# nm_temp_sens.net
KiCad netlist of a schematic drawn in Altium Designer
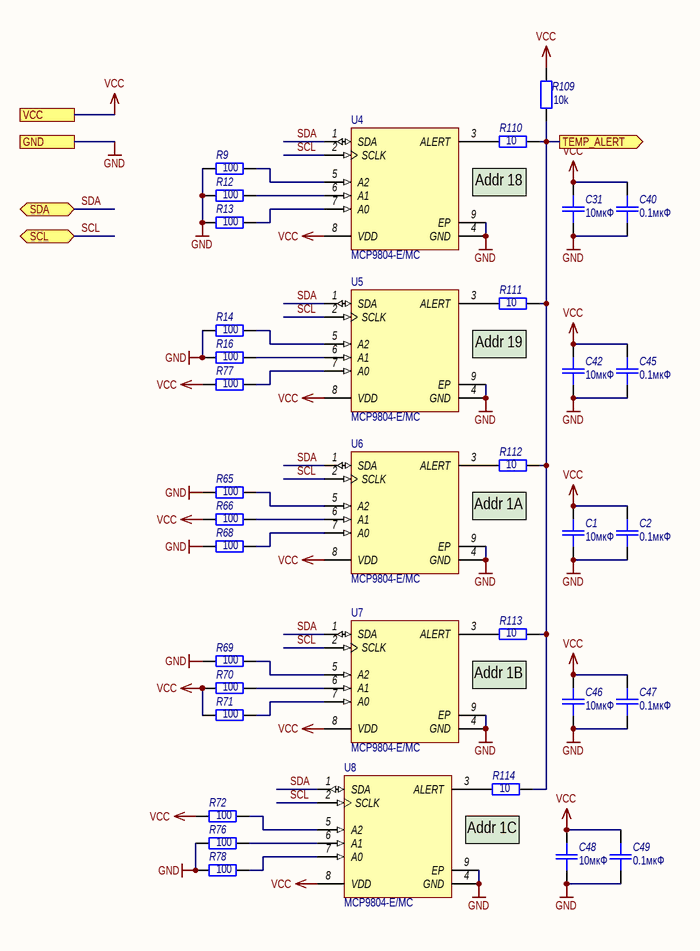
[diagram p0: nm_temp_sens.SchDoc]

(export (version "E")
  (design (tool "Eeschema 10.0.6"))
  (components
    (comp (ref "C1")
      (value "10мкФ")
      (footprint "SMD_C0603")
      (description "Capacitor")
      (libsource (lib "Passive") (part "Capacitor"))
    )
    (comp (ref "C2")
      (value "0.1мкФ")
      (footprint "SMD_C0603")
      (description "Capacitor")
      (libsource (lib "Passive") (part "Capacitor"))
    )
    (comp (ref "C31")
      (value "10мкФ")
      (footprint "SMD_C0603")
      (description "Capacitor")
      (libsource (lib "Passive") (part "Capacitor"))
    )
    (comp (ref "C40")
      (value "0.1мкФ")
      (footprint "SMD_C0603")
      (description "Capacitor")
      (libsource (lib "Passive") (part "Capacitor"))
    )
    (comp (ref "C42")
      (value "10мкФ")
      (footprint "SMD_C0603")
      (description "Capacitor")
      (libsource (lib "Passive") (part "Capacitor"))
    )
    (comp (ref "C45")
      (value "0.1мкФ")
      (footprint "SMD_C0603")
      (description "Capacitor")
      (libsource (lib "Passive") (part "Capacitor"))
    )
    (comp (ref "C46")
      (value "10мкФ")
      (footprint "SMD_C0603")
      (description "Capacitor")
      (libsource (lib "Passive") (part "Capacitor"))
    )
    (comp (ref "C47")
      (value "0.1мкФ")
      (footprint "SMD_C0603")
      (description "Capacitor")
      (libsource (lib "Passive") (part "Capacitor"))
    )
    (comp (ref "C48")
      (value "10мкФ")
      (footprint "SMD_C0603")
      (description "Capacitor")
      (libsource (lib "Passive") (part "Capacitor"))
    )
    (comp (ref "C49")
      (value "0.1мкФ")
      (footprint "SMD_C0603")
      (description "Capacitor")
      (libsource (lib "Passive") (part "Capacitor"))
    )
    (comp (ref "R9")
      (value "100")
      (footprint "SMD_0603")
      (description "Resistor")
      (libsource (lib "Passive") (part "Resistor"))
    )
    (comp (ref "R12")
      (value "100")
      (footprint "SMD_0603")
      (description "Resistor")
      (libsource (lib "Passive") (part "Resistor"))
    )
    (comp (ref "R13")
      (value "100")
      (footprint "SMD_0603")
      (description "Resistor")
      (libsource (lib "Passive") (part "Resistor"))
    )
    (comp (ref "R14")
      (value "100")
      (footprint "SMD_0603")
      (description "Resistor")
      (libsource (lib "Passive") (part "Resistor"))
    )
    (comp (ref "R16")
      (value "100")
      (footprint "SMD_0603")
      (description "Resistor")
      (libsource (lib "Passive") (part "Resistor"))
    )
    (comp (ref "R65")
      (value "100")
      (footprint "SMD_0603")
      (description "Resistor")
      (libsource (lib "Passive") (part "Resistor"))
    )
    (comp (ref "R66")
      (value "100")
      (footprint "SMD_0603")
      (description "Resistor")
      (libsource (lib "Passive") (part "Resistor"))
    )
    (comp (ref "R68")
      (value "100")
      (footprint "SMD_0603")
      (description "Resistor")
      (libsource (lib "Passive") (part "Resistor"))
    )
    (comp (ref "R69")
      (value "100")
      (footprint "SMD_0603")
      (description "Resistor")
      (libsource (lib "Passive") (part "Resistor"))
    )
    (comp (ref "R70")
      (value "100")
      (footprint "SMD_0603")
      (description "Resistor")
      (libsource (lib "Passive") (part "Resistor"))
    )
    (comp (ref "R71")
      (value "100")
      (footprint "SMD_0603")
      (description "Resistor")
      (libsource (lib "Passive") (part "Resistor"))
    )
    (comp (ref "R72")
      (value "100")
      (footprint "SMD_0603")
      (description "Resistor")
      (libsource (lib "Passive") (part "Resistor"))
    )
    (comp (ref "R76")
      (value "100")
      (footprint "SMD_0603")
      (description "Resistor")
      (libsource (lib "Passive") (part "Resistor"))
    )
    (comp (ref "R77")
      (value "100")
      (footprint "SMD_0603")
      (description "Resistor")
      (libsource (lib "Passive") (part "Resistor"))
    )
    (comp (ref "R78")
      (value "100")
      (footprint "SMD_0603")
      (description "Resistor")
      (libsource (lib "Passive") (part "Resistor"))
    )
    (comp (ref "R109")
      (value "10k")
      (footprint "SMD_0603")
      (description "Resistor")
      (libsource (lib "") (part "Resistor_1"))
    )
    (comp (ref "R110")
      (value "10")
      (footprint "SMD_0603")
      (description "Resistor")
      (libsource (lib "Passive") (part "Resistor"))
    )
    (comp (ref "R111")
      (value "10")
      (footprint "SMD_0603")
      (description "Resistor")
      (libsource (lib "Passive") (part "Resistor"))
    )
    (comp (ref "R112")
      (value "10")
      (footprint "SMD_0603")
      (description "Resistor")
      (libsource (lib "Passive") (part "Resistor"))
    )
    (comp (ref "R113")
      (value "10")
      (footprint "SMD_0603")
      (description "Resistor")
      (libsource (lib "Passive") (part "Resistor"))
    )
    (comp (ref "R114")
      (value "10")
      (footprint "SMD_0603")
      (description "Resistor")
      (libsource (lib "Passive") (part "Resistor"))
    )
    (comp (ref "U4")
      (value "MCP9804-E/MC")
      (footprint "DFN-MC8")
      (description "±0.25°C Typ. Accuracy Digital Temperature Sensor, 8-Pin DFN, Extended Temperature")
      (libsource (lib "MCP9804") (part "CMP-0192-00111-1"))
    )
    (comp (ref "U5")
      (value "MCP9804-E/MC")
      (footprint "DFN-MC8")
      (description "±0.25°C Typ. Accuracy Digital Temperature Sensor, 8-Pin DFN, Extended Temperature")
      (libsource (lib "MCP9804") (part "CMP-0192-00111-1"))
    )
    (comp (ref "U6")
      (value "MCP9804-E/MC")
      (footprint "DFN-MC8")
      (description "±0.25°C Typ. Accuracy Digital Temperature Sensor, 8-Pin DFN, Extended Temperature")
      (libsource (lib "MCP9804") (part "CMP-0192-00111-1"))
    )
    (comp (ref "U7")
      (value "MCP9804-E/MC")
      (footprint "DFN-MC8")
      (description "±0.25°C Typ. Accuracy Digital Temperature Sensor, 8-Pin DFN, Extended Temperature")
      (libsource (lib "MCP9804") (part "CMP-0192-00111-1"))
    )
    (comp (ref "U8")
      (value "MCP9804-E/MC")
      (footprint "DFN-MC8")
      (description "±0.25°C Typ. Accuracy Digital Temperature Sensor, 8-Pin DFN, Extended Temperature")
      (libsource (lib "MCP9804") (part "CMP-0192-00111-1"))
    )
  )
  (nets
    (net (code "1") (name "/SCL") (class "Default")
      (node (ref "U4") (pin "2") (pinfunction "SCLK_2") (pintype "input"))
      (node (ref "U5") (pin "2") (pinfunction "SCLK_2") (pintype "input"))
      (node (ref "U6") (pin "2") (pinfunction "SCLK_2") (pintype "input"))
      (node (ref "U7") (pin "2") (pinfunction "SCLK_2") (pintype "input"))
      (node (ref "U8") (pin "2") (pinfunction "SCLK_2") (pintype "input"))
    )
    (net (code "2") (name "/SDA") (class "Default")
      (node (ref "U4") (pin "1") (pinfunction "SDA_1") (pintype "bidirectional"))
      (node (ref "U5") (pin "1") (pinfunction "SDA_1") (pintype "bidirectional"))
      (node (ref "U6") (pin "1") (pinfunction "SDA_1") (pintype "bidirectional"))
      (node (ref "U7") (pin "1") (pinfunction "SDA_1") (pintype "bidirectional"))
      (node (ref "U8") (pin "1") (pinfunction "SDA_1") (pintype "bidirectional"))
    )
    (net (code "3") (name "/TEMP_ALERT") (class "Default")
      (node (ref "R109") (pin "1") (pinfunction "1_1") (pintype "passive"))
      (node (ref "R110") (pin "2") (pinfunction "2_2") (pintype "passive"))
      (node (ref "R111") (pin "2") (pinfunction "2_2") (pintype "passive"))
      (node (ref "R112") (pin "2") (pinfunction "2_2") (pintype "passive"))
      (node (ref "R113") (pin "2") (pinfunction "2_2") (pintype "passive"))
      (node (ref "R114") (pin "2") (pinfunction "2_2") (pintype "passive"))
    )
    (net (code "4") (name "GND") (class "Default")
      (node (ref "C1") (pin "1") (pinfunction "1_1") (pintype "passive"))
      (node (ref "C2") (pin "1") (pinfunction "1_1") (pintype "passive"))
      (node (ref "C31") (pin "1") (pinfunction "1_1") (pintype "passive"))
      (node (ref "C40") (pin "1") (pinfunction "1_1") (pintype "passive"))
      (node (ref "C42") (pin "1") (pinfunction "1_1") (pintype "passive"))
      (node (ref "C45") (pin "1") (pinfunction "1_1") (pintype "passive"))
      (node (ref "C46") (pin "1") (pinfunction "1_1") (pintype "passive"))
      (node (ref "C47") (pin "1") (pinfunction "1_1") (pintype "passive"))
      (node (ref "C48") (pin "1") (pinfunction "1_1") (pintype "passive"))
      (node (ref "C49") (pin "1") (pinfunction "1_1") (pintype "passive"))
      (node (ref "R12") (pin "1") (pinfunction "1_1") (pintype "passive"))
      (node (ref "R13") (pin "1") (pinfunction "1_1") (pintype "passive"))
      (node (ref "R14") (pin "1") (pinfunction "1_1") (pintype "passive"))
      (node (ref "R16") (pin "1") (pinfunction "1_1") (pintype "passive"))
      (node (ref "R65") (pin "1") (pinfunction "1_1") (pintype "passive"))
      (node (ref "R68") (pin "1") (pinfunction "1_1") (pintype "passive"))
      (node (ref "R69") (pin "1") (pinfunction "1_1") (pintype "passive"))
      (node (ref "R76") (pin "1") (pinfunction "1_1") (pintype "passive"))
      (node (ref "R78") (pin "1") (pinfunction "1_1") (pintype "passive"))
      (node (ref "R9") (pin "1") (pinfunction "1_1") (pintype "passive"))
      (node (ref "U4") (pin "4") (pinfunction "GND_4") (pintype "power_in"))
      (node (ref "U4") (pin "9") (pinfunction "EP_9") (pintype "passive"))
      (node (ref "U5") (pin "4") (pinfunction "GND_4") (pintype "power_in"))
      (node (ref "U5") (pin "9") (pinfunction "EP_9") (pintype "passive"))
      (node (ref "U6") (pin "4") (pinfunction "GND_4") (pintype "power_in"))
      (node (ref "U6") (pin "9") (pinfunction "EP_9") (pintype "passive"))
      (node (ref "U7") (pin "4") (pinfunction "GND_4") (pintype "power_in"))
      (node (ref "U7") (pin "9") (pinfunction "EP_9") (pintype "passive"))
      (node (ref "U8") (pin "4") (pinfunction "GND_4") (pintype "power_in"))
      (node (ref "U8") (pin "9") (pinfunction "EP_9") (pintype "passive"))
    )
    (net (code "5") (name "Net-(U4-A0)") (class "Default")
      (node (ref "R13") (pin "2") (pinfunction "2_2") (pintype "passive"))
      (node (ref "U4") (pin "7") (pinfunction "A0_7") (pintype "input"))
    )
    (net (code "6") (name "Net-(U4-A1)") (class "Default")
      (node (ref "R12") (pin "2") (pinfunction "2_2") (pintype "passive"))
      (node (ref "U4") (pin "6") (pinfunction "A1_6") (pintype "input"))
    )
    (net (code "7") (name "Net-(U4-A2)") (class "Default")
      (node (ref "R9") (pin "2") (pinfunction "2_2") (pintype "passive"))
      (node (ref "U4") (pin "5") (pinfunction "A2_5") (pintype "input"))
    )
    (net (code "8") (name "Net-(U4-ALERT)") (class "Default")
      (node (ref "R110") (pin "1") (pinfunction "1_1") (pintype "passive"))
      (node (ref "U4") (pin "3") (pinfunction "ALERT_3") (pintype "open_collector"))
    )
    (net (code "9") (name "Net-(U5-A0)") (class "Default")
      (node (ref "R77") (pin "2") (pinfunction "2_2") (pintype "passive"))
      (node (ref "U5") (pin "7") (pinfunction "A0_7") (pintype "input"))
    )
    (net (code "10") (name "Net-(U5-A1)") (class "Default")
      (node (ref "R16") (pin "2") (pinfunction "2_2") (pintype "passive"))
      (node (ref "U5") (pin "6") (pinfunction "A1_6") (pintype "input"))
    )
    (net (code "11") (name "Net-(U5-A2)") (class "Default")
      (node (ref "R14") (pin "2") (pinfunction "2_2") (pintype "passive"))
      (node (ref "U5") (pin "5") (pinfunction "A2_5") (pintype "input"))
    )
    (net (code "12") (name "Net-(U5-ALERT)") (class "Default")
      (node (ref "R111") (pin "1") (pinfunction "1_1") (pintype "passive"))
      (node (ref "U5") (pin "3") (pinfunction "ALERT_3") (pintype "open_collector"))
    )
    (net (code "13") (name "Net-(U6-A0)") (class "Default")
      (node (ref "R68") (pin "2") (pinfunction "2_2") (pintype "passive"))
      (node (ref "U6") (pin "7") (pinfunction "A0_7") (pintype "input"))
    )
    (net (code "14") (name "Net-(U6-A1)") (class "Default")
      (node (ref "R66") (pin "2") (pinfunction "2_2") (pintype "passive"))
      (node (ref "U6") (pin "6") (pinfunction "A1_6") (pintype "input"))
    )
    (net (code "15") (name "Net-(U6-A2)") (class "Default")
      (node (ref "R65") (pin "2") (pinfunction "2_2") (pintype "passive"))
      (node (ref "U6") (pin "5") (pinfunction "A2_5") (pintype "input"))
    )
    (net (code "16") (name "Net-(U6-ALERT)") (class "Default")
      (node (ref "R112") (pin "1") (pinfunction "1_1") (pintype "passive"))
      (node (ref "U6") (pin "3") (pinfunction "ALERT_3") (pintype "open_collector"))
    )
    (net (code "17") (name "Net-(U7-A0)") (class "Default")
      (node (ref "R71") (pin "2") (pinfunction "2_2") (pintype "passive"))
      (node (ref "U7") (pin "7") (pinfunction "A0_7") (pintype "input"))
    )
    (net (code "18") (name "Net-(U7-A1)") (class "Default")
      (node (ref "R70") (pin "2") (pinfunction "2_2") (pintype "passive"))
      (node (ref "U7") (pin "6") (pinfunction "A1_6") (pintype "input"))
    )
    (net (code "19") (name "Net-(U7-A2)") (class "Default")
      (node (ref "R69") (pin "2") (pinfunction "2_2") (pintype "passive"))
      (node (ref "U7") (pin "5") (pinfunction "A2_5") (pintype "input"))
    )
    (net (code "20") (name "Net-(U7-ALERT)") (class "Default")
      (node (ref "R113") (pin "1") (pinfunction "1_1") (pintype "passive"))
      (node (ref "U7") (pin "3") (pinfunction "ALERT_3") (pintype "open_collector"))
    )
    (net (code "21") (name "Net-(U8-A0)") (class "Default")
      (node (ref "R78") (pin "2") (pinfunction "2_2") (pintype "passive"))
      (node (ref "U8") (pin "7") (pinfunction "A0_7") (pintype "input"))
    )
    (net (code "22") (name "Net-(U8-A1)") (class "Default")
      (node (ref "R76") (pin "2") (pinfunction "2_2") (pintype "passive"))
      (node (ref "U8") (pin "6") (pinfunction "A1_6") (pintype "input"))
    )
    (net (code "23") (name "Net-(U8-A2)") (class "Default")
      (node (ref "R72") (pin "2") (pinfunction "2_2") (pintype "passive"))
      (node (ref "U8") (pin "5") (pinfunction "A2_5") (pintype "input"))
    )
    (net (code "24") (name "Net-(U8-ALERT)") (class "Default")
      (node (ref "R114") (pin "1") (pinfunction "1_1") (pintype "passive"))
      (node (ref "U8") (pin "3") (pinfunction "ALERT_3") (pintype "open_collector"))
    )
    (net (code "25") (name "VCC") (class "Default")
      (node (ref "C1") (pin "2") (pinfunction "2_2") (pintype "passive"))
      (node (ref "C2") (pin "2") (pinfunction "2_2") (pintype "passive"))
      (node (ref "C31") (pin "2") (pinfunction "2_2") (pintype "passive"))
      (node (ref "C40") (pin "2") (pinfunction "2_2") (pintype "passive"))
      (node (ref "C42") (pin "2") (pinfunction "2_2") (pintype "passive"))
      (node (ref "C45") (pin "2") (pinfunction "2_2") (pintype "passive"))
      (node (ref "C46") (pin "2") (pinfunction "2_2") (pintype "passive"))
      (node (ref "C47") (pin "2") (pinfunction "2_2") (pintype "passive"))
      (node (ref "C48") (pin "2") (pinfunction "2_2") (pintype "passive"))
      (node (ref "C49") (pin "2") (pinfunction "2_2") (pintype "passive"))
      (node (ref "R109") (pin "2") (pinfunction "2_2") (pintype "passive"))
      (node (ref "R66") (pin "1") (pinfunction "1_1") (pintype "passive"))
      (node (ref "R70") (pin "1") (pinfunction "1_1") (pintype "passive"))
      (node (ref "R71") (pin "1") (pinfunction "1_1") (pintype "passive"))
      (node (ref "R72") (pin "1") (pinfunction "1_1") (pintype "passive"))
      (node (ref "R77") (pin "1") (pinfunction "1_1") (pintype "passive"))
      (node (ref "U4") (pin "8") (pinfunction "VDD_8") (pintype "power_in"))
      (node (ref "U5") (pin "8") (pinfunction "VDD_8") (pintype "power_in"))
      (node (ref "U6") (pin "8") (pinfunction "VDD_8") (pintype "power_in"))
      (node (ref "U7") (pin "8") (pinfunction "VDD_8") (pintype "power_in"))
      (node (ref "U8") (pin "8") (pinfunction "VDD_8") (pintype "power_in"))
    )
  )
)
